# NNP-DWG-165-001-000_BP2_Microcontroller_.net
KiCad netlist of a schematic drawn in Altium Designer
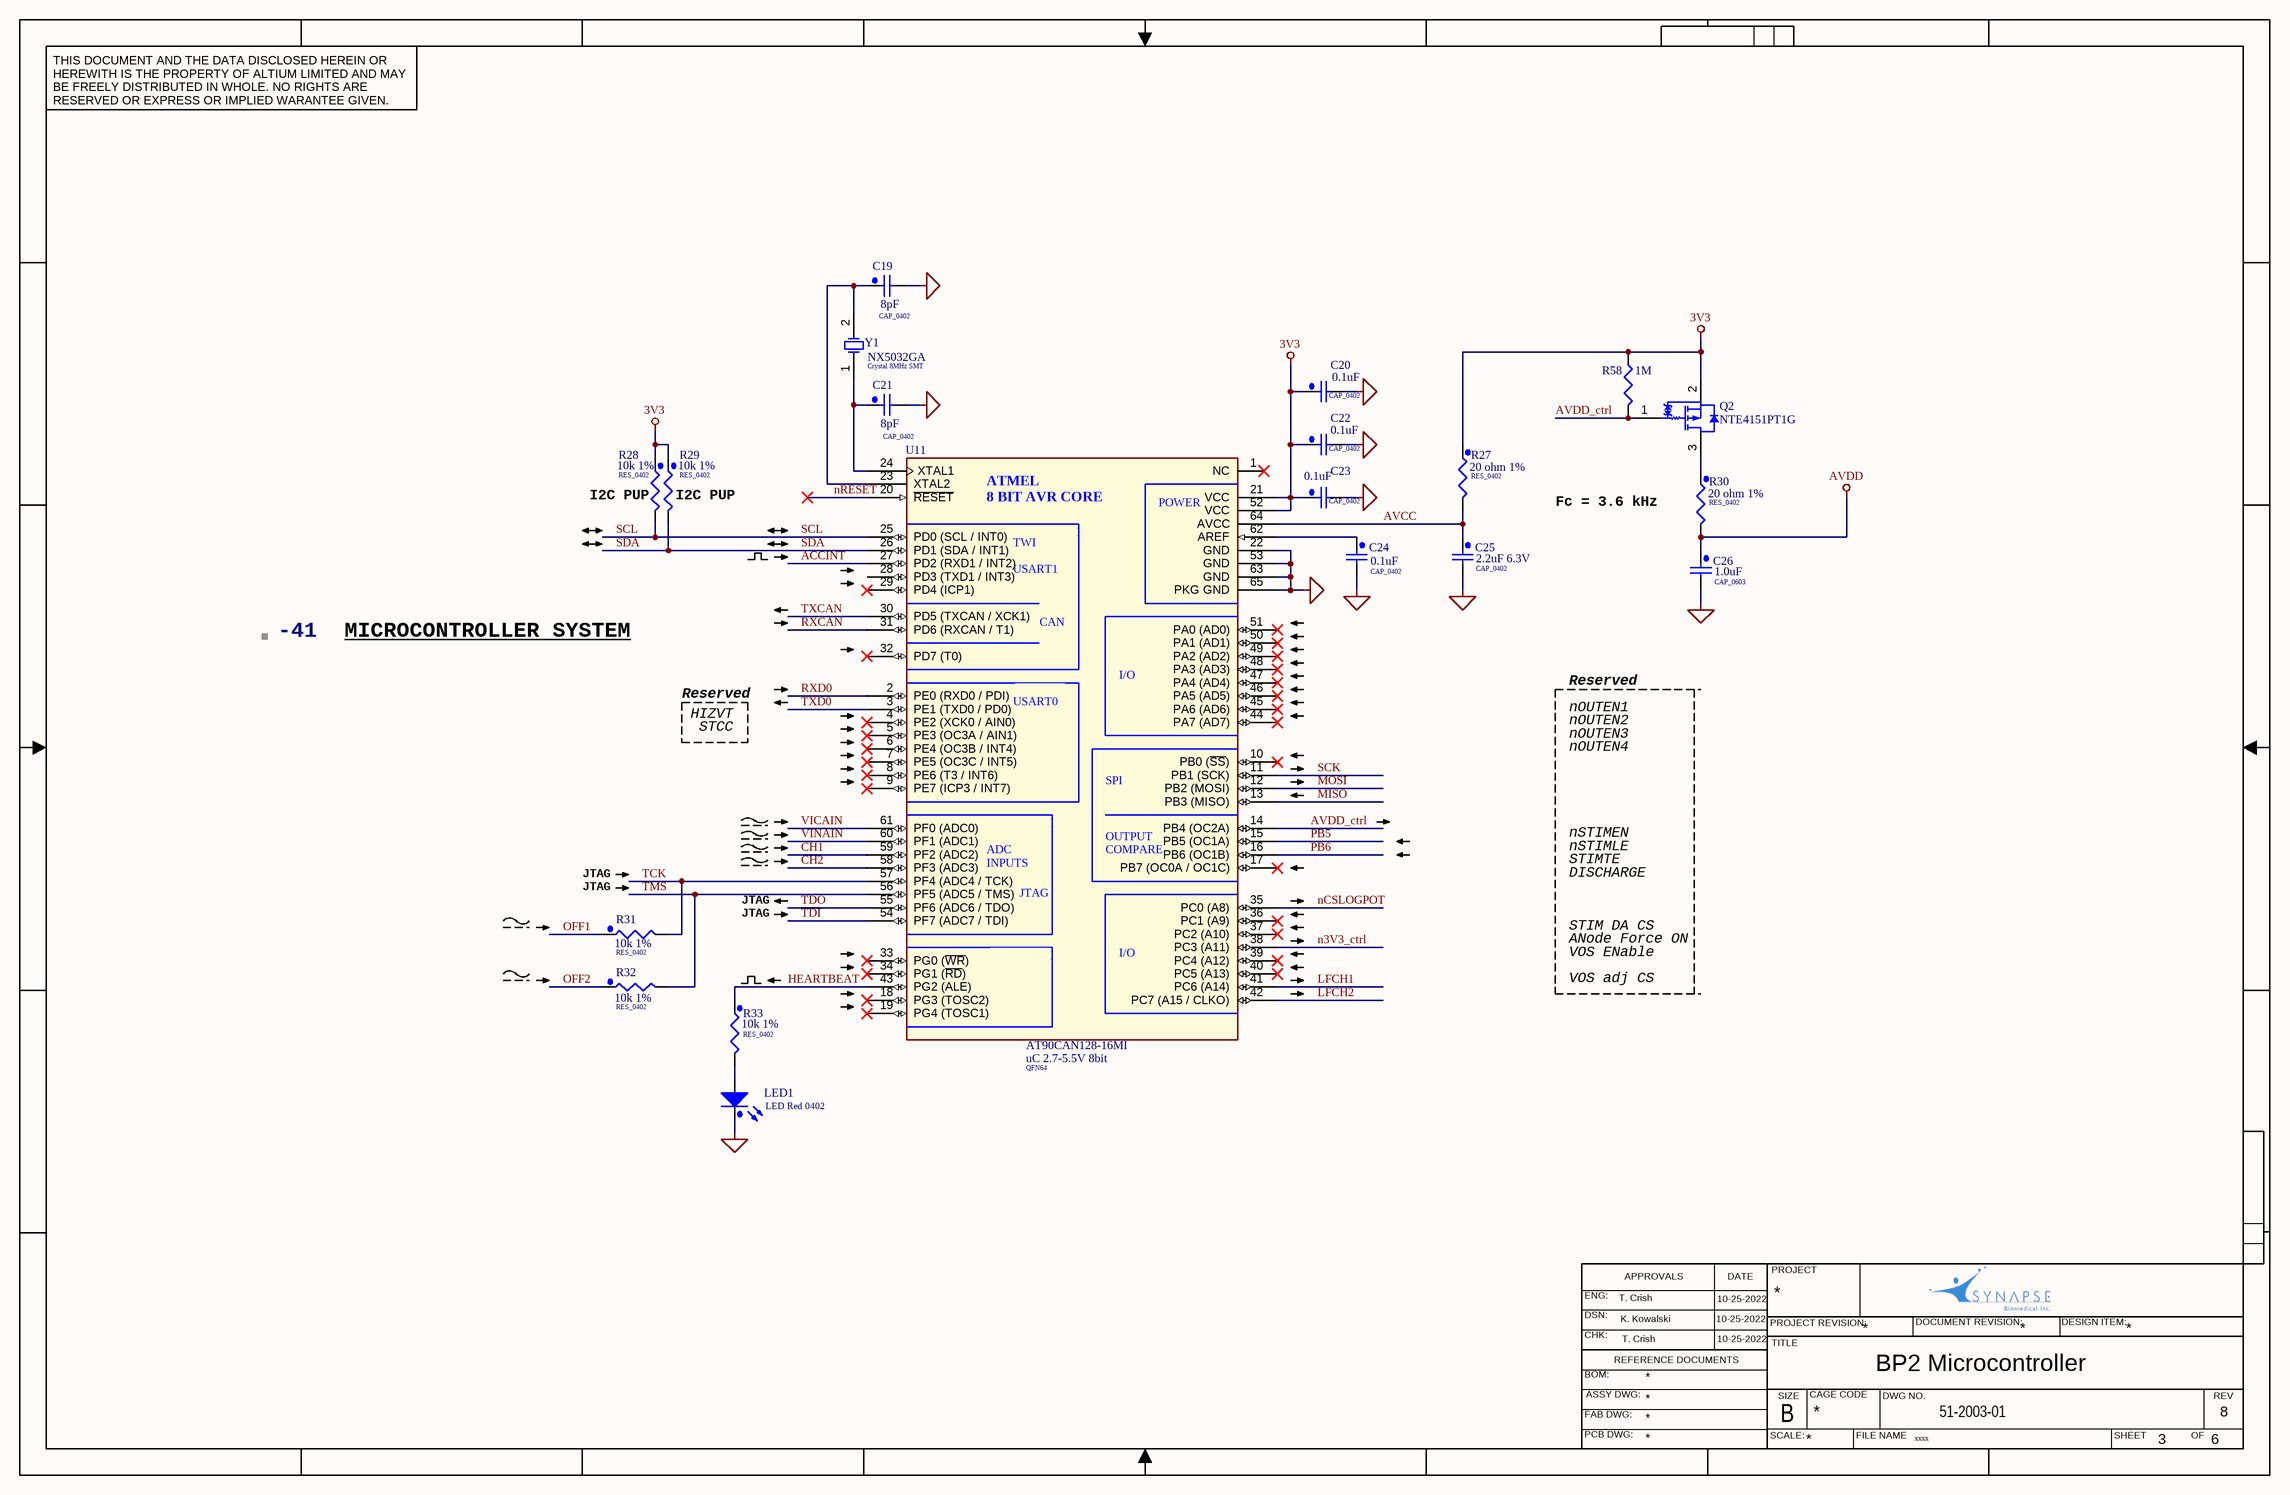
[diagram p0: NNP-DWG-165-001-000 BP2 Microcontroller Pg 3 of 6.SchDoc]

(export (version "E")
  (design (tool "Eeschema 10.0.6"))
  (components
    (comp (ref "-41")
      (value "BOM_S1")
      (description "BOM item small graphic")
      (fields (field (name "XDESCRIPTION") "MICROCONTROLLER SYSTEM"))
      (libsource (lib "BOM_sym") (part "BOM_S1"))
    )
    (comp (ref "C19")
      (value "8pF")
      (footprint "CAP_0402")
      (description "8pF, 50V, C0G, 0402, 10%, RoHS")
      (fields
        (field (name "MFR") "Murata Electronics North America")
        (field (name "PACKAGEDESCRIPTION") "CAP_0402")
        (field (name "MPN") "GRM1555C1H8R0DA01D")
      )
      (libsource (lib "NNPS Integrated Parts") (part "ECJ-0EC1H080D"))
    )
    (comp (ref "C20")
      (value "0.1uF")
      (footprint "CAP_0402")
      (description "0.1uF, 16V, X7R, 0402, RoHS")
      (fields
        (field (name "MFR") "Murata Electronics North America")
        (field (name "PACKAGEDESCRIPTION") "CAP_0402")
        (field (name "MPN") "GRM155R71C104KA88D")
      )
      (libsource (lib "NNPS Integrated Parts") (part "GRM155R71C104KA88D"))
    )
    (comp (ref "C21")
      (value "8pF")
      (footprint "CAP_0402")
      (description "8pF, 50V, C0G, 0402, 10%, RoHS")
      (fields
        (field (name "MFR") "Murata Electronics North America")
        (field (name "PACKAGEDESCRIPTION") "CAP_0402")
        (field (name "MPN") "GRM1555C1H8R0DA01D")
      )
      (libsource (lib "NNPS Integrated Parts") (part "ECJ-0EC1H080D"))
    )
    (comp (ref "C22")
      (value "0.1uF")
      (footprint "CAP_0402")
      (description "0.1uF, 16V, X7R, 0402, RoHS")
      (fields
        (field (name "MFR") "Murata Electronics North America")
        (field (name "PACKAGEDESCRIPTION") "CAP_0402")
        (field (name "MPN") "GRM155R71C104KA88D")
      )
      (libsource (lib "NNPS Integrated Parts") (part "GRM155R71C104KA88D"))
    )
    (comp (ref "C23")
      (value "0.1uF")
      (footprint "CAP_0402")
      (description "0.1uF, 16V, X7R, 0402, RoHS")
      (fields
        (field (name "MFR") "Murata Electronics North America")
        (field (name "PACKAGEDESCRIPTION") "CAP_0402")
        (field (name "MPN") "GRM155R71C104KA88D")
      )
      (libsource (lib "NNPS Integrated Parts") (part "GRM155R71C104KA88D"))
    )
    (comp (ref "C24")
      (value "0.1uF")
      (footprint "CAP_0402")
      (description "0.1uF, 16V, X7R, 0402, RoHS")
      (fields
        (field (name "MFR") "Murata Electronics North America")
        (field (name "PACKAGEDESCRIPTION") "CAP_0402")
        (field (name "MPN") "GRM155R71C104KA88D")
      )
      (libsource (lib "NNPS Integrated Parts") (part "GRM155R71C104KA88D"))
    )
    (comp (ref "C25")
      (value "2.2uF 6.3V")
      (footprint "CAP_0402")
      (description "2.2uF, 6.3V, X5R, 0402, 20%, RoHS")
      (fields
        (field (name "MFR") "Murata Electronics North America")
        (field (name "PACKAGEDESCRIPTION") "CAP_0402")
        (field (name "MPN") "GRM155R60J225ME15D")
      )
      (libsource (lib "NNPS Integrated Parts") (part "6R3R07X225MV4T"))
    )
    (comp (ref "C26")
      (value "1.0uF")
      (footprint "CAP_0402")
      (description "1.0uF, 6.3V, X5R, 20%, 0402, RoHS")
      (fields
        (field (name "MFR") "TDK Corp")
        (field (name "PACKAGEDESCRIPTION") "CAP_0603")
        (field (name "MPN") "CGA3E1X7R1C105K080AC")
      )
      (libsource (lib "NNPS Integrated Parts") (part "6R3R07X225MV4T"))
    )
    (comp (ref "LED1")
      (value "LED Red 0402")
      (footprint "LED_0402_RED")
      (description "LED, Red, 0402, 20mA ,2V, 140mcd, RoHS")
      (fields (field (name "MFR") "Lumex") (field (name "MPN") "SML-LX0402SIC-TR"))
      (libsource (lib "NNPS Integrated Parts") (part "SML-LX0402SIC-TR"))
    )
    (comp (ref "Q2")
      (value "NTE4151PT1G")
      (footprint "ON Semi MOSFETs:ONSC-SC-89-3-463C-02_V")
      (fields (field (name "MANUFACTURER") "On Semiconductor"))
      (libsource (lib "altium-import") (part "root_2_mirrored_CMP-1058-00652-1_"))
    )
    (comp (ref "R27")
      (value "20 ohm 1%")
      (footprint "RES_0402")
      (description "20 ohm, 1%, 0402, 1%, RoHS")
      (fields
        (field (name "MFR") "Vishay")
        (field (name "PACKAGEDESCRIPTION") "RES_0402")
        (field (name "MPN") "CRCW040220R0FKED")
      )
      (libsource (lib "NNPS Integrated Parts") (part "CRCW040220R0FKED"))
    )
    (comp (ref "R28")
      (value "10k 1%")
      (footprint "RES_0402")
      (description "10.0k ohm, 1%, 1/16W, smd, 0402, RoHS")
      (fields
        (field (name "MFR") "Vishay Dale")
        (field (name "PACKAGEDESCRIPTION") "RES_0402")
        (field (name "MPN") "CRCW040210K0FKED")
      )
      (libsource (lib "NNPS Integrated Parts") (part "MCR01MZPF1002"))
    )
    (comp (ref "R29")
      (value "10k 1%")
      (footprint "RES_0402")
      (description "10.0k ohm, 1%, 1/16W, smd, 0402, RoHS")
      (fields
        (field (name "MFR") "Vishay Dale")
        (field (name "PACKAGEDESCRIPTION") "RES_0402")
        (field (name "MPN") "CRCW040210K0FKED")
      )
      (libsource (lib "NNPS Integrated Parts") (part "MCR01MZPF1002"))
    )
    (comp (ref "R30")
      (value "20 ohm 1%")
      (footprint "RES_0402")
      (description "20 ohm, 1%, 0402, 1%, RoHS")
      (fields
        (field (name "MFR") "Vishay")
        (field (name "PACKAGEDESCRIPTION") "RES_0402")
        (field (name "MPN") "CRCW040220R0FKED")
      )
      (libsource (lib "NNPS Integrated Parts") (part "CRCW040220R0FKED"))
    )
    (comp (ref "R31")
      (value "10k 1%")
      (footprint "RES_0402")
      (description "10.0k ohm, 1%, 1/16W, smd, 0402, RoHS")
      (fields
        (field (name "MFR") "Vishay Dale")
        (field (name "PACKAGEDESCRIPTION") "RES_0402")
        (field (name "MPN") "CRCW040210K0FKED")
      )
      (libsource (lib "NNPS Integrated Parts") (part "MCR01MZPF1002"))
    )
    (comp (ref "R32")
      (value "10k 1%")
      (footprint "RES_0402")
      (description "10.0k ohm, 1%, 1/16W, smd, 0402, RoHS")
      (fields
        (field (name "MFR") "Vishay Dale")
        (field (name "PACKAGEDESCRIPTION") "RES_0402")
        (field (name "MPN") "CRCW040210K0FKED")
      )
      (libsource (lib "NNPS Integrated Parts") (part "MCR01MZPF1002"))
    )
    (comp (ref "R33")
      (value "10k 1%")
      (footprint "RES_0402")
      (description "10.0k ohm, 1%, 1/16W, smd, 0402, RoHS")
      (fields
        (field (name "MFR") "Vishay Dale")
        (field (name "PACKAGEDESCRIPTION") "RES_0402")
        (field (name "MPN") "CRCW040210K0FKED")
      )
      (libsource (lib "NNPS Integrated Parts") (part "MCR01MZPF1002"))
    )
    (comp (ref "R58")
      (value "1M")
      (footprint "CHIP_0402N")
      (description "Resistor 1M 0402 1% 63mW")
      (fields (field (name "MANUFACTURER") "Rohm") (field (name "Comment") "1M_0402 Resistor"))
      (libsource (lib "NNPS Integrated Parts1") (part "R_1M_0402"))
    )
    (comp (ref "U11")
      (value "uC 2.7-5.5V 8bit")
      (footprint "QFN64")
      (description "uC, 2.7-5.5V, 8bit, QFN64, RoHS")
      (fields
        (field (name "MFR") "Atmel")
        (field (name "PACKAGEDESCRIPTION") "QFN64")
        (field (name "MPN") "AT90CAN128-16MI")
      )
      (libsource (lib "NNPS Integrated Parts") (part "AT90CAN128-16MI"))
    )
    (comp (ref "Y1")
      (value "Crystal 8MHz SMT")
      (footprint "NX5032GA")
      (fields (field (name "MFR") "NDK") (field (name "MPN") "NX5032GA"))
      (libsource (lib "NNPS Integrated Parts") (part "NX5032GA"))
    )
  )
  (nets
    (net (code "1") (name "/ACCINT") (class "Default")
      (node (ref "U11") (pin "27") (pinfunction "PD2_(RXD1_/_INT2)_27") (pintype "bidirectional"))
    )
    (net (code "2") (name "/AVCC") (class "Default")
      (node (ref "C25") (pin "1") (pinfunction "1_1") (pintype "passive"))
      (node (ref "R27") (pin "2") (pinfunction "2_2") (pintype "passive"))
      (node (ref "U11") (pin "64") (pinfunction "AVCC_64") (pintype "power_in"))
    )
    (net (code "3") (name "/AVDD_ctrl") (class "Default")
      (node (ref "Q2") (pin "1") (pinfunction "G_1") (pintype "passive"))
      (node (ref "R58") (pin "2") (pinfunction "2_2") (pintype "passive"))
      (node (ref "U11") (pin "14") (pinfunction "PB4_(OC2A)_14") (pintype "bidirectional"))
    )
    (net (code "4") (name "/CH1") (class "Default")
      (node (ref "U11") (pin "59") (pinfunction "PF2_(ADC2)_59") (pintype "bidirectional"))
    )
    (net (code "5") (name "/CH2") (class "Default")
      (node (ref "U11") (pin "58") (pinfunction "PF3_(ADC3)_58") (pintype "bidirectional"))
    )
    (net (code "6") (name "/HEARTBEAT") (class "Default")
      (node (ref "R33") (pin "1") (pinfunction "1_1") (pintype "passive"))
      (node (ref "U11") (pin "43") (pinfunction "PG2_(ALE)_43") (pintype "bidirectional"))
    )
    (net (code "7") (name "/LFCH1") (class "Default")
      (node (ref "U11") (pin "41") (pinfunction "PC6_(A14)_41") (pintype "bidirectional"))
    )
    (net (code "8") (name "/LFCH2") (class "Default")
      (node (ref "U11") (pin "42") (pinfunction "PC7_(A15_/_CLKO)_42") (pintype "bidirectional"))
    )
    (net (code "9") (name "/MISO") (class "Default")
      (node (ref "U11") (pin "13") (pinfunction "PB3_(MISO)_13") (pintype "bidirectional"))
    )
    (net (code "10") (name "/MOSI") (class "Default")
      (node (ref "U11") (pin "12") (pinfunction "PB2_(MOSI)_12") (pintype "bidirectional"))
    )
    (net (code "11") (name "/OFF1") (class "Default")
      (node (ref "R31") (pin "1") (pinfunction "1_1") (pintype "passive"))
    )
    (net (code "12") (name "/OFF2") (class "Default")
      (node (ref "R32") (pin "1") (pinfunction "1_1") (pintype "passive"))
    )
    (net (code "13") (name "/PB5") (class "Default")
      (node (ref "U11") (pin "15") (pinfunction "PB5_(OC1A)_15") (pintype "bidirectional"))
    )
    (net (code "14") (name "/PB6") (class "Default")
      (node (ref "U11") (pin "16") (pinfunction "PB6_(OC1B)_16") (pintype "bidirectional"))
    )
    (net (code "15") (name "/RXCAN") (class "Default")
      (node (ref "U11") (pin "31") (pinfunction "PD6_(RXCAN_/_T1)_31") (pintype "bidirectional"))
    )
    (net (code "16") (name "/RXD0") (class "Default")
      (node (ref "U11") (pin "2") (pinfunction "PE0_(RXD0_/_PDI)_2") (pintype "bidirectional"))
    )
    (net (code "17") (name "/SCK") (class "Default")
      (node (ref "U11") (pin "11") (pinfunction "PB1_(SCK)_11") (pintype "bidirectional"))
    )
    (net (code "18") (name "/SCL") (class "Default")
      (node (ref "R28") (pin "2") (pinfunction "2_2") (pintype "passive"))
      (node (ref "U11") (pin "25") (pinfunction "PD0_(SCL_/_INT0)_25") (pintype "bidirectional"))
    )
    (net (code "19") (name "/SDA") (class "Default")
      (node (ref "R29") (pin "2") (pinfunction "2_2") (pintype "passive"))
      (node (ref "U11") (pin "26") (pinfunction "PD1_(SDA_/_INT1)_26") (pintype "bidirectional"))
    )
    (net (code "20") (name "/TCK") (class "Default")
      (node (ref "R31") (pin "2") (pinfunction "2_2") (pintype "passive"))
      (node (ref "U11") (pin "57") (pinfunction "PF4_(ADC4_/_TCK)_57") (pintype "bidirectional"))
    )
    (net (code "21") (name "/TDI") (class "Default")
      (node (ref "U11") (pin "54") (pinfunction "PF7_(ADC7_/_TDI)_54") (pintype "bidirectional"))
    )
    (net (code "22") (name "/TDO") (class "Default")
      (node (ref "U11") (pin "55") (pinfunction "PF6_(ADC6_/_TDO)_55") (pintype "bidirectional"))
    )
    (net (code "23") (name "/TMS") (class "Default")
      (node (ref "R32") (pin "2") (pinfunction "2_2") (pintype "passive"))
      (node (ref "U11") (pin "56") (pinfunction "PF5_(ADC5_/_TMS)_56") (pintype "bidirectional"))
    )
    (net (code "24") (name "/TXCAN") (class "Default")
      (node (ref "U11") (pin "30") (pinfunction "PD5_(TXCAN_/_XCK1)_30") (pintype "bidirectional"))
    )
    (net (code "25") (name "/TXD0") (class "Default")
      (node (ref "U11") (pin "3") (pinfunction "PE1_(TXD0_/_PD0)_3") (pintype "bidirectional"))
    )
    (net (code "26") (name "/VICAIN") (class "Default")
      (node (ref "U11") (pin "61") (pinfunction "PF0_(ADC0)_61") (pintype "bidirectional"))
    )
    (net (code "27") (name "/VINAIN") (class "Default")
      (node (ref "U11") (pin "60") (pinfunction "PF1_(ADC1)_60") (pintype "bidirectional"))
    )
    (net (code "28") (name "/n3V3_ctrl") (class "Default")
      (node (ref "U11") (pin "38") (pinfunction "PC3_(A11)_38") (pintype "bidirectional"))
    )
    (net (code "29") (name "/nCSLOGPOT") (class "Default")
      (node (ref "U11") (pin "35") (pinfunction "PC0_(A8)_35") (pintype "bidirectional"))
    )
    (net (code "30") (name "/nRESET") (class "Default")
      (node (ref "U11") (pin "20") (pinfunction "~{RESET}_20") (pintype "input+no_connect"))
    )
    (net (code "31") (name "3V3") (class "Default")
      (node (ref "C20") (pin "1") (pinfunction "1_1") (pintype "passive"))
      (node (ref "C22") (pin "1") (pinfunction "1_1") (pintype "passive"))
      (node (ref "C23") (pin "1") (pinfunction "1_1") (pintype "passive"))
      (node (ref "Q2") (pin "2") (pinfunction "S_2") (pintype "passive"))
      (node (ref "R27") (pin "1") (pinfunction "1_1") (pintype "passive"))
      (node (ref "R28") (pin "1") (pinfunction "1_1") (pintype "passive"))
      (node (ref "R29") (pin "1") (pinfunction "1_1") (pintype "passive"))
      (node (ref "R58") (pin "1") (pinfunction "1_1") (pintype "passive"))
      (node (ref "U11") (pin "21") (pinfunction "VCC_21") (pintype "power_in"))
      (node (ref "U11") (pin "52") (pinfunction "VCC_52") (pintype "power_in"))
    )
    (net (code "32") (name "AVDD") (class "Default")
      (node (ref "C26") (pin "1") (pinfunction "1_1") (pintype "passive"))
      (node (ref "R30") (pin "2") (pinfunction "2_2") (pintype "passive"))
    )
    (net (code "33") (name "GND") (class "Default")
      (node (ref "C19") (pin "2") (pinfunction "2_2") (pintype "passive"))
      (node (ref "C20") (pin "2") (pinfunction "2_2") (pintype "passive"))
      (node (ref "C21") (pin "2") (pinfunction "2_2") (pintype "passive"))
      (node (ref "C22") (pin "2") (pinfunction "2_2") (pintype "passive"))
      (node (ref "C23") (pin "2") (pinfunction "2_2") (pintype "passive"))
      (node (ref "C24") (pin "2") (pinfunction "2_2") (pintype "passive"))
      (node (ref "C25") (pin "2") (pinfunction "2_2") (pintype "passive"))
      (node (ref "C26") (pin "2") (pinfunction "2_2") (pintype "passive"))
      (node (ref "LED1") (pin "1") (pinfunction "C_1") (pintype "passive"))
      (node (ref "U11") (pin "22") (pinfunction "GND_22") (pintype "power_in"))
      (node (ref "U11") (pin "53") (pinfunction "GND_53") (pintype "power_in"))
      (node (ref "U11") (pin "63") (pinfunction "GND_63") (pintype "power_in"))
      (node (ref "U11") (pin "65") (pinfunction "PKG_GND_65") (pintype "power_in"))
    )
    (net (code "34") (name "Net-(LED1-A)") (class "Default")
      (node (ref "LED1") (pin "2") (pinfunction "A_2") (pintype "passive"))
      (node (ref "R33") (pin "2") (pinfunction "2_2") (pintype "passive"))
    )
    (net (code "35") (name "Net-(Q2-D)") (class "Default")
      (node (ref "Q2") (pin "3") (pinfunction "D_3") (pintype "passive"))
      (node (ref "R30") (pin "1") (pinfunction "1_1") (pintype "passive"))
    )
    (net (code "36") (name "Net-(U11-AREF)") (class "Default")
      (node (ref "C24") (pin "1") (pinfunction "1_1") (pintype "passive"))
      (node (ref "U11") (pin "62") (pinfunction "AREF_62") (pintype "input"))
    )
    (net (code "37") (name "Net-(U11-XTAL1)") (class "Default")
      (node (ref "C21") (pin "1") (pinfunction "1_1") (pintype "passive"))
      (node (ref "U11") (pin "24") (pinfunction "XTAL1_24") (pintype "passive"))
      (node (ref "Y1") (pin "1") (pinfunction "OSC1_1") (pintype "passive"))
    )
    (net (code "38") (name "Net-(U11-XTAL2)") (class "Default")
      (node (ref "C19") (pin "1") (pinfunction "1_1") (pintype "passive"))
      (node (ref "U11") (pin "23") (pinfunction "XTAL2_23") (pintype "passive"))
      (node (ref "Y1") (pin "2") (pinfunction "OSC2_2") (pintype "passive"))
    )
    (net (code "39") (name "unconnected-(U11-NC-Pad1)") (class "Default")
      (node (ref "U11") (pin "1") (pinfunction "NC_1") (pintype "passive+no_connect"))
    )
    (net (code "40") (name "unconnected-(U11-PA0_(AD0)-Pad51)") (class "Default")
      (node (ref "U11") (pin "51") (pinfunction "PA0_(AD0)_51") (pintype "bidirectional+no_connect"))
    )
    (net (code "41") (name "unconnected-(U11-PA1_(AD1)-Pad50)") (class "Default")
      (node (ref "U11") (pin "50") (pinfunction "PA1_(AD1)_50") (pintype "bidirectional+no_connect"))
    )
    (net (code "42") (name "unconnected-(U11-PA2_(AD2)-Pad49)") (class "Default")
      (node (ref "U11") (pin "49") (pinfunction "PA2_(AD2)_49") (pintype "bidirectional+no_connect"))
    )
    (net (code "43") (name "unconnected-(U11-PA3_(AD3)-Pad48)") (class "Default")
      (node (ref "U11") (pin "48") (pinfunction "PA3_(AD3)_48") (pintype "bidirectional+no_connect"))
    )
    (net (code "44") (name "unconnected-(U11-PA4_(AD4)-Pad47)") (class "Default")
      (node (ref "U11") (pin "47") (pinfunction "PA4_(AD4)_47") (pintype "bidirectional+no_connect"))
    )
    (net (code "45") (name "unconnected-(U11-PA5_(AD5)-Pad46)") (class "Default")
      (node (ref "U11") (pin "46") (pinfunction "PA5_(AD5)_46") (pintype "bidirectional+no_connect"))
    )
    (net (code "46") (name "unconnected-(U11-PA6_(AD6)-Pad45)") (class "Default")
      (node (ref "U11") (pin "45") (pinfunction "PA6_(AD6)_45") (pintype "bidirectional+no_connect"))
    )
    (net (code "47") (name "unconnected-(U11-PA7_(AD7)-Pad44)") (class "Default")
      (node (ref "U11") (pin "44") (pinfunction "PA7_(AD7)_44") (pintype "bidirectional+no_connect"))
    )
    (net (code "48") (name "unconnected-(U11-PB0_(~{SS})-Pad10)") (class "Default")
      (node (ref "U11") (pin "10") (pinfunction "PB0_(~{SS})_10") (pintype "bidirectional+no_connect"))
    )
    (net (code "49") (name "unconnected-(U11-PB7_(OC0A_{slash}_OC1C)-Pad17)") (class "Default")
      (node (ref "U11") (pin "17") (pinfunction "PB7_(OC0A_/_OC1C)_17") (pintype "bidirectional+no_connect"))
    )
    (net (code "50") (name "unconnected-(U11-PC1_(A9)-Pad36)") (class "Default")
      (node (ref "U11") (pin "36") (pinfunction "PC1_(A9)_36") (pintype "bidirectional+no_connect"))
    )
    (net (code "51") (name "unconnected-(U11-PC2_(A10)-Pad37)") (class "Default")
      (node (ref "U11") (pin "37") (pinfunction "PC2_(A10)_37") (pintype "bidirectional+no_connect"))
    )
    (net (code "52") (name "unconnected-(U11-PC4_(A12)-Pad39)") (class "Default")
      (node (ref "U11") (pin "39") (pinfunction "PC4_(A12)_39") (pintype "bidirectional+no_connect"))
    )
    (net (code "53") (name "unconnected-(U11-PC5_(A13)-Pad40)") (class "Default")
      (node (ref "U11") (pin "40") (pinfunction "PC5_(A13)_40") (pintype "bidirectional+no_connect"))
    )
    (net (code "54") (name "unconnected-(U11-PD3_(TXD1_{slash}_INT3)-Pad28)") (class "Default")
      (node (ref "U11") (pin "28") (pinfunction "PD3_(TXD1_/_INT3)_28") (pintype "bidirectional"))
    )
    (net (code "55") (name "unconnected-(U11-PD4_(ICP1)-Pad29)") (class "Default")
      (node (ref "U11") (pin "29") (pinfunction "PD4_(ICP1)_29") (pintype "bidirectional+no_connect"))
    )
    (net (code "56") (name "unconnected-(U11-PD7_(T0)-Pad32)") (class "Default")
      (node (ref "U11") (pin "32") (pinfunction "PD7_(T0)_32") (pintype "bidirectional+no_connect"))
    )
    (net (code "57") (name "unconnected-(U11-PE2_(XCK0_{slash}_AIN0)-Pad4)") (class "Default")
      (node (ref "U11") (pin "4") (pinfunction "PE2_(XCK0_/_AIN0)_4") (pintype "bidirectional+no_connect"))
    )
    (net (code "58") (name "unconnected-(U11-PE3_(OC3A_{slash}_AIN1)-Pad5)") (class "Default")
      (node (ref "U11") (pin "5") (pinfunction "PE3_(OC3A_/_AIN1)_5") (pintype "bidirectional+no_connect"))
    )
    (net (code "59") (name "unconnected-(U11-PE4_(OC3B_{slash}_INT4)-Pad6)") (class "Default")
      (node (ref "U11") (pin "6") (pinfunction "PE4_(OC3B_/_INT4)_6") (pintype "bidirectional+no_connect"))
    )
    (net (code "60") (name "unconnected-(U11-PE5_(OC3C_{slash}_INT5)-Pad7)") (class "Default")
      (node (ref "U11") (pin "7") (pinfunction "PE5_(OC3C_/_INT5)_7") (pintype "bidirectional+no_connect"))
    )
    (net (code "61") (name "unconnected-(U11-PE6_(T3_{slash}_INT6)-Pad8)") (class "Default")
      (node (ref "U11") (pin "8") (pinfunction "PE6_(T3_/_INT6)_8") (pintype "bidirectional+no_connect"))
    )
    (net (code "62") (name "unconnected-(U11-PE7_(ICP3_{slash}_INT7)-Pad9)") (class "Default")
      (node (ref "U11") (pin "9") (pinfunction "PE7_(ICP3_/_INT7)_9") (pintype "bidirectional+no_connect"))
    )
    (net (code "63") (name "unconnected-(U11-PG0_(~{WR})-Pad33)") (class "Default")
      (node (ref "U11") (pin "33") (pinfunction "PG0_(~{WR})_33") (pintype "bidirectional+no_connect"))
    )
    (net (code "64") (name "unconnected-(U11-PG1_(~{RD})-Pad34)") (class "Default")
      (node (ref "U11") (pin "34") (pinfunction "PG1_(~{RD})_34") (pintype "bidirectional+no_connect"))
    )
    (net (code "65") (name "unconnected-(U11-PG3_(TOSC2)-Pad18)") (class "Default")
      (node (ref "U11") (pin "18") (pinfunction "PG3_(TOSC2)_18") (pintype "bidirectional+no_connect"))
    )
    (net (code "66") (name "unconnected-(U11-PG4_(TOSC1)-Pad19)") (class "Default")
      (node (ref "U11") (pin "19") (pinfunction "PG4_(TOSC1)_19") (pintype "bidirectional+no_connect"))
    )
  )
)
